# Top.net
KiCad netlist of a schematic drawn in Altium Designer
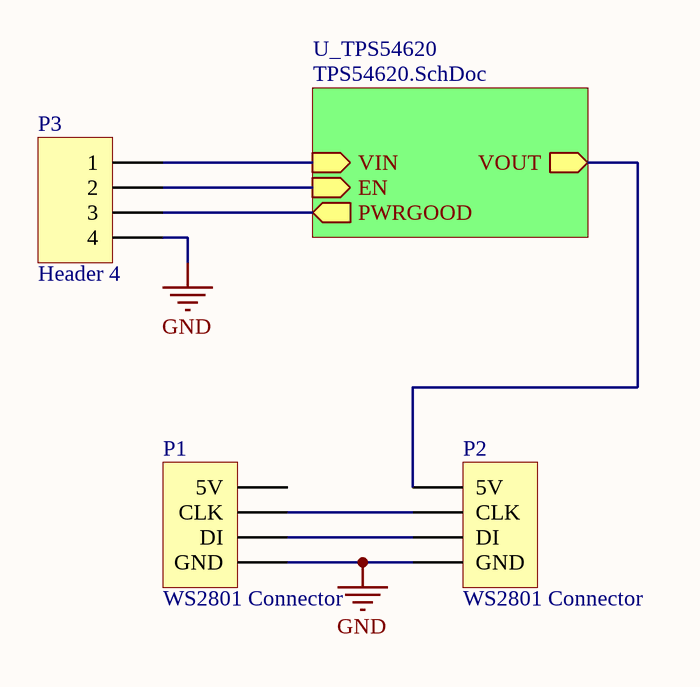
[diagram p0: Top.SchDoc]

(export (version "E")
  (design (tool "Eeschema 10.0.6"))
  (components
    (comp (ref "P1")
      (value "WS2801 Connector")
      (footprint "HDR1X4")
      (description "Header, 4-Pin")
      (fields (field (name "PUBLISHER") "Altium Limited"))
      (libsource (lib "") (part "WS2801 Connector_1"))
    )
    (comp (ref "P2")
      (value "WS2801 Connector")
      (footprint "HDR1X4")
      (description "Header, 4-Pin")
      (fields (field (name "PUBLISHER") "Altium Limited"))
      (libsource (lib "Miscellaneous Connectors") (part "WS2801 Connector"))
    )
    (comp (ref "P3")
      (value "Header 4")
      (footprint "HDR1X4")
      (description "Header, 4-Pin")
      (fields (field (name "PUBLISHER") "Altium Limited"))
      (libsource (lib "Miscellaneous Connectors") (part "Header 4"))
    )
  )
  (nets
    (net (code "1") (name "/EN") (class "Default")
      (node (ref "P3") (pin "2") (pinfunction "2_2") (pintype "passive"))
    )
    (net (code "2") (name "/PWRGOOD") (class "Default")
      (node (ref "P3") (pin "3") (pinfunction "3_3") (pintype "passive"))
    )
    (net (code "3") (name "/VIN") (class "Default")
      (node (ref "P3") (pin "1") (pinfunction "1_1") (pintype "passive"))
    )
    (net (code "4") (name "/VOUT") (class "Default")
      (node (ref "P2") (pin "1") (pinfunction "5V_1") (pintype "passive"))
    )
    (net (code "5") (name "GND") (class "Default")
      (node (ref "P1") (pin "4") (pinfunction "GND_4") (pintype "passive"))
      (node (ref "P2") (pin "4") (pinfunction "GND_4") (pintype "passive"))
      (node (ref "P3") (pin "4") (pinfunction "4_4") (pintype "passive"))
    )
    (net (code "6") (name "Net-(P1-CLK)") (class "Default")
      (node (ref "P1") (pin "2") (pinfunction "CLK_2") (pintype "passive"))
      (node (ref "P2") (pin "2") (pinfunction "CLK_2") (pintype "passive"))
    )
    (net (code "7") (name "Net-(P1-DI)") (class "Default")
      (node (ref "P1") (pin "3") (pinfunction "DI_3") (pintype "passive"))
      (node (ref "P2") (pin "3") (pinfunction "DI_3") (pintype "passive"))
    )
    (net (code "8") (name "unconnected-(P1-5V-Pad1)") (class "Default")
      (node (ref "P1") (pin "1") (pinfunction "5V_1") (pintype "passive"))
    )
  )
)
